# KinetisCANBoard.net
KiCad netlist of a schematic drawn in Altium Designer
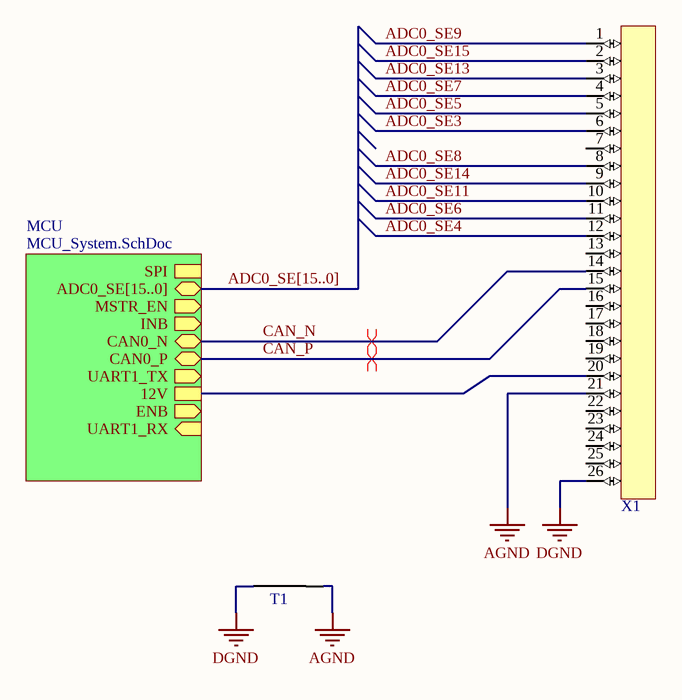
[diagram p0: KinetisCANBoard.SchDoc]

(export (version "E")
  (design (tool "Eeschema 10.0.6"))
  (components
    (comp (ref "T1")
      (value "Net Tie")
      (footprint "Net Tie 10mil")
      (libsource (lib "Components") (part "Net Tie"))
    )
    (comp (ref "X1")
      (value "TE Superseal 26 POS")
      (footprint "TE_SUPERSEAL_26")
      (libsource (lib "Components") (part "TE Superseal 26 POS"))
    )
  )
  (nets
    (net (code "6") (name "/12V") (class "Default") (node (ref "X1") (pin "20") (pintype "bidirectional")))
    (net (code "7") (name "/ADC0_SE3") (class "Default")
      (node (ref "X1") (pin "6") (pintype "bidirectional"))
    )
    (net (code "8") (name "/ADC0_SE4") (class "Default")
      (node (ref "X1") (pin "12") (pintype "bidirectional"))
    )
    (net (code "9") (name "/ADC0_SE5") (class "Default")
      (node (ref "X1") (pin "5") (pintype "bidirectional"))
    )
    (net (code "10") (name "/ADC0_SE6") (class "Default")
      (node (ref "X1") (pin "11") (pintype "bidirectional"))
    )
    (net (code "11") (name "/ADC0_SE7") (class "Default")
      (node (ref "X1") (pin "4") (pintype "bidirectional"))
    )
    (net (code "12") (name "/ADC0_SE8") (class "Default")
      (node (ref "X1") (pin "8") (pintype "bidirectional"))
    )
    (net (code "13") (name "/ADC0_SE9") (class "Default")
      (node (ref "X1") (pin "1") (pintype "bidirectional"))
    )
    (net (code "14") (name "/ADC0_SE11") (class "Default")
      (node (ref "X1") (pin "10") (pintype "bidirectional"))
    )
    (net (code "15") (name "/ADC0_SE13") (class "Default")
      (node (ref "X1") (pin "3") (pintype "bidirectional"))
    )
    (net (code "16") (name "/ADC0_SE14") (class "Default")
      (node (ref "X1") (pin "9") (pintype "bidirectional"))
    )
    (net (code "17") (name "/ADC0_SE15") (class "Default")
      (node (ref "X1") (pin "2") (pintype "bidirectional"))
    )
    (net (code "19") (name "/CAN_N") (class "Default") (node (ref "X1") (pin "14") (pintype "bidirectional")))
    (net (code "20") (name "/CAN_P") (class "Default") (node (ref "X1") (pin "15") (pintype "bidirectional")))
    (net (code "27") (name "AGND") (class "Default")
      (node (ref "T1") (pin "2") (pinfunction "2_2") (pintype "passive"))
      (node (ref "X1") (pin "21") (pintype "bidirectional"))
    )
    (net (code "28") (name "DGND") (class "Default")
      (node (ref "T1") (pin "1") (pinfunction "1_1") (pintype "passive"))
      (node (ref "X1") (pin "26") (pintype "bidirectional"))
    )
    (net (code "29") (name "unconnected-(X1-Pad7)") (class "Default")
      (node (ref "X1") (pin "7") (pintype "bidirectional"))
    )
    (net (code "30") (name "unconnected-(X1-Pad13)") (class "Default")
      (node (ref "X1") (pin "13") (pintype "bidirectional"))
    )
    (net (code "31") (name "unconnected-(X1-Pad16)") (class "Default")
      (node (ref "X1") (pin "16") (pintype "bidirectional"))
    )
    (net (code "32") (name "unconnected-(X1-Pad17)") (class "Default")
      (node (ref "X1") (pin "17") (pintype "bidirectional"))
    )
    (net (code "33") (name "unconnected-(X1-Pad18)") (class "Default")
      (node (ref "X1") (pin "18") (pintype "bidirectional"))
    )
    (net (code "34") (name "unconnected-(X1-Pad19)") (class "Default")
      (node (ref "X1") (pin "19") (pintype "bidirectional"))
    )
    (net (code "35") (name "unconnected-(X1-Pad22)") (class "Default")
      (node (ref "X1") (pin "22") (pintype "bidirectional"))
    )
    (net (code "36") (name "unconnected-(X1-Pad23)") (class "Default")
      (node (ref "X1") (pin "23") (pintype "bidirectional"))
    )
    (net (code "37") (name "unconnected-(X1-Pad24)") (class "Default")
      (node (ref "X1") (pin "24") (pintype "bidirectional"))
    )
    (net (code "38") (name "unconnected-(X1-Pad25)") (class "Default")
      (node (ref "X1") (pin "25") (pintype "bidirectional"))
    )
  )
)
